# New_Project.net
KiCad netlist of a schematic drawn in EasyEDA
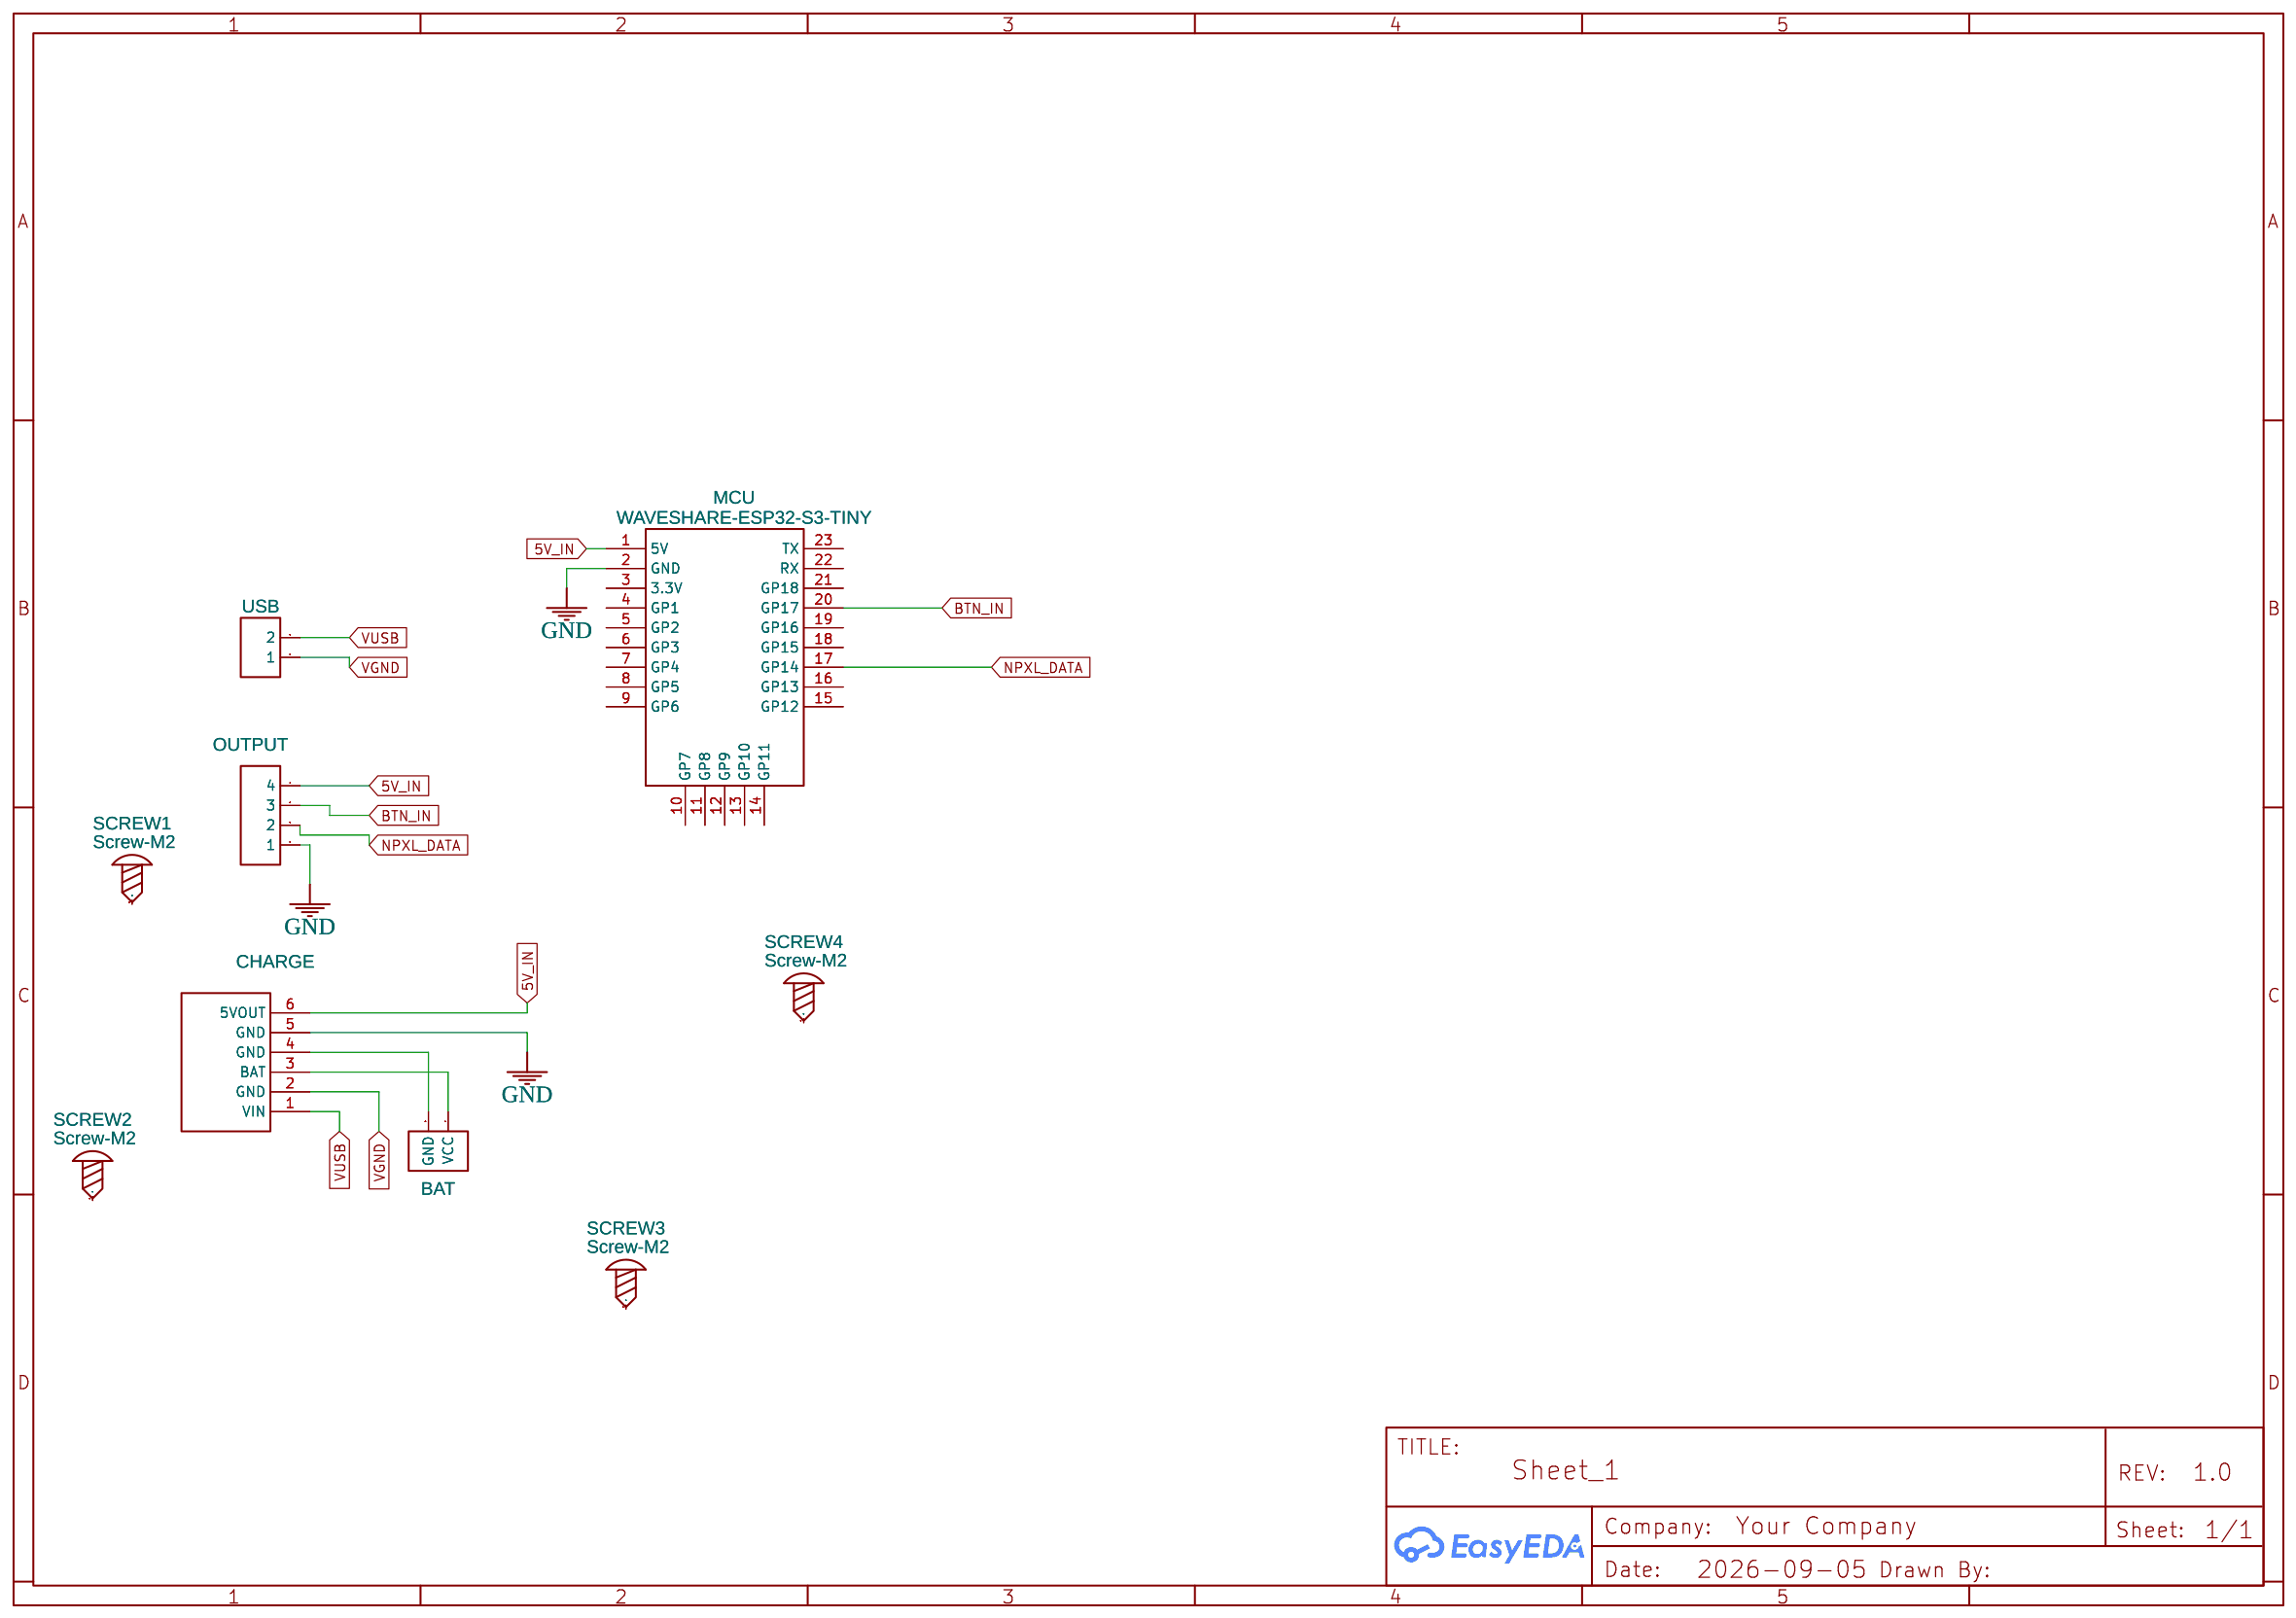
[diagram p0: schematic sheet]

(export (version "E")
  (design (tool "Eeschema 10.0.6"))
  (components
    (comp (ref "BAT") (value "Input") (libsource (lib "") (part "HDR-F-2.54_1x2")))
    (comp (ref "CHARGE")
      (value "2A_5V_CHARGE_DISCHARGE_INTEGRATED_3.7V_4.2V_LITHIUM_BATTERY_BOOST_WASN")
      (fields
        (field (name "Manufacturer Part") "2A_5V_Charge_Discharge_Integrated_3.7V_4.2V_Lithium_Battery_Boost_Mobile")
      )
      (libsource (lib "") (part "2A_5V_CHARGE_DISCHARGE_INTEGRATED_3.7V_4.2V_LITHIUM_BATTERY_BOOST_WASN"))
    )
    (comp (ref "MCU")
      (value "WAVESHARE-ESP32-S3-TINY")
      (fields
        (field (name "Manufacturer Part") "ESP32-S3 Mini Development Board")
        (field (name "Manufacturer") "WAVESHARE")
      )
      (libsource (lib "") (part "WAVESHARE-ESP32-S3-TINY"))
    )
    (comp (ref "OUTPUT") (value "output") (libsource (lib "") (part "HDR-F-2.54_1x4")))
    (comp (ref "SCREW1") (value "Screw-M2") (libsource (lib "") (part "Screw-M2")))
    (comp (ref "SCREW2") (value "Screw-M2") (libsource (lib "") (part "Screw-M2")))
    (comp (ref "SCREW3") (value "Screw-M2") (libsource (lib "") (part "Screw-M2")))
    (comp (ref "SCREW4") (value "Screw-M2") (libsource (lib "") (part "Screw-M2")))
    (comp (ref "USB") (value "HDR-M-2.54_1x2") (libsource (lib "") (part "HDR-M-2.54_1x2")))
  )
  (nets
    (net (code "1") (name "5V_IN") (class "Default")
      (node (ref "CHARGE") (pin "6") (pinfunction "5VOUT_6") (pintype "unspecified"))
      (node (ref "MCU") (pin "1") (pinfunction "5V_1") (pintype "unspecified"))
      (node (ref "OUTPUT") (pin "4") (pinfunction "4_4") (pintype "unspecified"))
    )
    (net (code "2") (name "BTN_IN") (class "Default")
      (node (ref "MCU") (pin "20") (pinfunction "GP17_20") (pintype "unspecified"))
      (node (ref "OUTPUT") (pin "3") (pinfunction "3_3") (pintype "unspecified"))
    )
    (net (code "3") (name "GND") (class "Default")
      (node (ref "CHARGE") (pin "5") (pinfunction "GND_5") (pintype "unspecified"))
      (node (ref "MCU") (pin "2") (pinfunction "GND_2") (pintype "unspecified"))
      (node (ref "OUTPUT") (pin "1") (pinfunction "1_1") (pintype "unspecified"))
    )
    (net (code "4") (name "NPXL_DATA") (class "Default")
      (node (ref "MCU") (pin "17") (pinfunction "GP14_17") (pintype "unspecified"))
      (node (ref "OUTPUT") (pin "2") (pinfunction "2_2") (pintype "unspecified"))
    )
    (net (code "5") (name "Net-(BAT-GND)") (class "Default")
      (node (ref "BAT") (pin "2") (pinfunction "GND_2") (pintype "input"))
      (node (ref "CHARGE") (pin "4") (pinfunction "GND_4") (pintype "unspecified"))
    )
    (net (code "6") (name "Net-(BAT-VCC)") (class "Default")
      (node (ref "BAT") (pin "1") (pinfunction "VCC_1") (pintype "input"))
      (node (ref "CHARGE") (pin "3") (pinfunction "BAT_3") (pintype "unspecified"))
    )
    (net (code "7") (name "VGND") (class "Default")
      (node (ref "CHARGE") (pin "2") (pinfunction "GND_2") (pintype "unspecified"))
      (node (ref "USB") (pin "1") (pinfunction "1_1") (pintype "unspecified"))
    )
    (net (code "8") (name "VUSB") (class "Default")
      (node (ref "CHARGE") (pin "1") (pinfunction "VIN_1") (pintype "unspecified"))
      (node (ref "USB") (pin "2") (pinfunction "2_2") (pintype "unspecified"))
    )
    (net (code "9") (name "unconnected-(MCU-3.3V-Pad3)") (class "Default")
      (node (ref "MCU") (pin "3") (pinfunction "3.3V_3") (pintype "unspecified"))
    )
    (net (code "10") (name "unconnected-(MCU-GP1-Pad4)") (class "Default")
      (node (ref "MCU") (pin "4") (pinfunction "GP1_4") (pintype "unspecified"))
    )
    (net (code "11") (name "unconnected-(MCU-GP2-Pad5)") (class "Default")
      (node (ref "MCU") (pin "5") (pinfunction "GP2_5") (pintype "unspecified"))
    )
    (net (code "12") (name "unconnected-(MCU-GP3-Pad6)") (class "Default")
      (node (ref "MCU") (pin "6") (pinfunction "GP3_6") (pintype "unspecified"))
    )
    (net (code "13") (name "unconnected-(MCU-GP4-Pad7)") (class "Default")
      (node (ref "MCU") (pin "7") (pinfunction "GP4_7") (pintype "unspecified"))
    )
    (net (code "14") (name "unconnected-(MCU-GP5-Pad8)") (class "Default")
      (node (ref "MCU") (pin "8") (pinfunction "GP5_8") (pintype "unspecified"))
    )
    (net (code "15") (name "unconnected-(MCU-GP6-Pad9)") (class "Default")
      (node (ref "MCU") (pin "9") (pinfunction "GP6_9") (pintype "unspecified"))
    )
    (net (code "16") (name "unconnected-(MCU-GP7-Pad10)") (class "Default")
      (node (ref "MCU") (pin "10") (pinfunction "GP7_10") (pintype "unspecified"))
    )
    (net (code "17") (name "unconnected-(MCU-GP8-Pad11)") (class "Default")
      (node (ref "MCU") (pin "11") (pinfunction "GP8_11") (pintype "unspecified"))
    )
    (net (code "18") (name "unconnected-(MCU-GP9-Pad12)") (class "Default")
      (node (ref "MCU") (pin "12") (pinfunction "GP9_12") (pintype "unspecified"))
    )
    (net (code "19") (name "unconnected-(MCU-GP10-Pad13)") (class "Default")
      (node (ref "MCU") (pin "13") (pinfunction "GP10_13") (pintype "unspecified"))
    )
    (net (code "20") (name "unconnected-(MCU-GP11-Pad14)") (class "Default")
      (node (ref "MCU") (pin "14") (pinfunction "GP11_14") (pintype "unspecified"))
    )
    (net (code "21") (name "unconnected-(MCU-GP12-Pad15)") (class "Default")
      (node (ref "MCU") (pin "15") (pinfunction "GP12_15") (pintype "unspecified"))
    )
    (net (code "22") (name "unconnected-(MCU-GP13-Pad16)") (class "Default")
      (node (ref "MCU") (pin "16") (pinfunction "GP13_16") (pintype "unspecified"))
    )
    (net (code "23") (name "unconnected-(MCU-GP15-Pad18)") (class "Default")
      (node (ref "MCU") (pin "18") (pinfunction "GP15_18") (pintype "unspecified"))
    )
    (net (code "24") (name "unconnected-(MCU-GP16-Pad19)") (class "Default")
      (node (ref "MCU") (pin "19") (pinfunction "GP16_19") (pintype "unspecified"))
    )
    (net (code "25") (name "unconnected-(MCU-GP18-Pad21)") (class "Default")
      (node (ref "MCU") (pin "21") (pinfunction "GP18_21") (pintype "unspecified"))
    )
    (net (code "26") (name "unconnected-(MCU-RX-Pad22)") (class "Default")
      (node (ref "MCU") (pin "22") (pinfunction "RX_22") (pintype "unspecified"))
    )
    (net (code "27") (name "unconnected-(MCU-TX-Pad23)") (class "Default")
      (node (ref "MCU") (pin "23") (pinfunction "TX_23") (pintype "unspecified"))
    )
    (net (code "28") (name "unconnected-(SCREW1-Pad1)") (class "Default")
      (node (ref "SCREW1") (pin "1") (pinfunction "1_1") (pintype "unspecified"))
    )
    (net (code "29") (name "unconnected-(SCREW2-Pad1)") (class "Default")
      (node (ref "SCREW2") (pin "1") (pinfunction "1_1") (pintype "unspecified"))
    )
    (net (code "30") (name "unconnected-(SCREW3-Pad1)") (class "Default")
      (node (ref "SCREW3") (pin "1") (pinfunction "1_1") (pintype "unspecified"))
    )
    (net (code "31") (name "unconnected-(SCREW4-Pad1)") (class "Default")
      (node (ref "SCREW4") (pin "1") (pinfunction "1_1") (pintype "unspecified"))
    )
  )
)
